# RainbowClock.net
KiCad netlist of a schematic drawn in Altium Designer
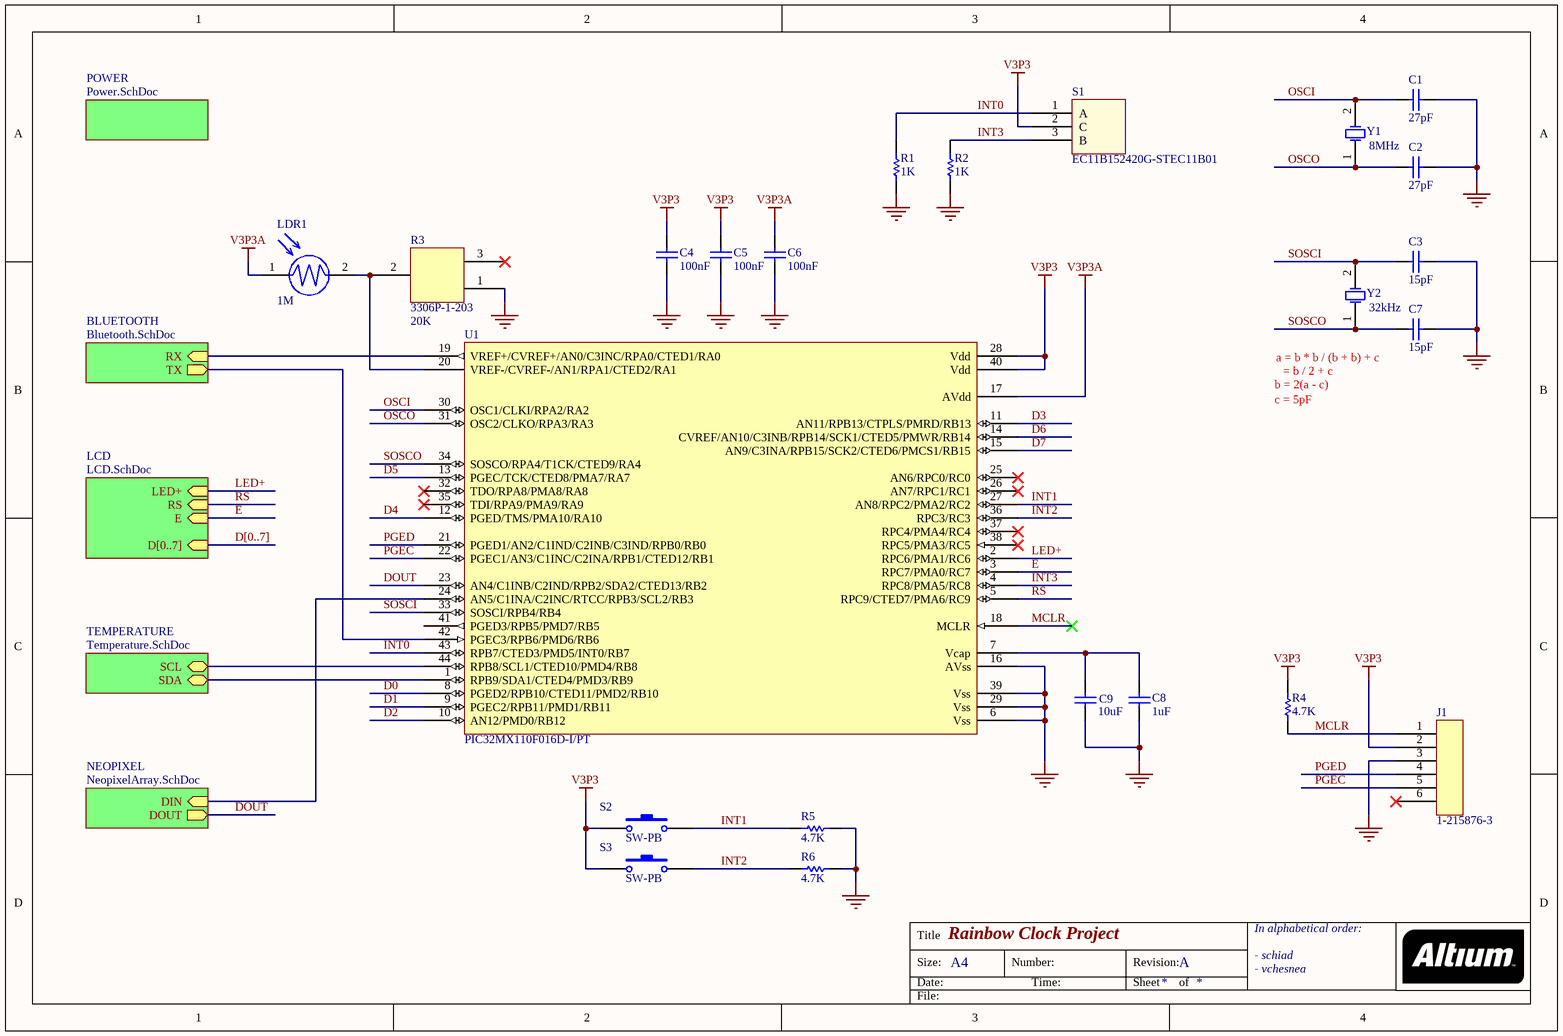
[diagram p0: RainbowClock.SchDoc]

(export (version "E")
  (design (tool "Eeschema 10.0.6"))
  (components
    (comp (ref "C1")
      (value "27pF")
      (footprint "CAP0603")
      (description "Capacitor")
      (libsource (lib "Miscellaneous Devices") (part "Cap"))
    )
    (comp (ref "C2")
      (value "27pF")
      (footprint "CAP0603")
      (description "Capacitor")
      (libsource (lib "Miscellaneous Devices") (part "Cap"))
    )
    (comp (ref "C3")
      (value "15pF")
      (footprint "CAP0603")
      (description "Capacitor")
      (libsource (lib "Miscellaneous Devices") (part "Cap"))
    )
    (comp (ref "C4")
      (value "100nF")
      (footprint "CAP0603")
      (description "Capacitor")
      (libsource (lib "Miscellaneous Devices") (part "Cap"))
    )
    (comp (ref "C5")
      (value "100nF")
      (footprint "CAP0603")
      (description "Capacitor")
      (libsource (lib "Miscellaneous Devices") (part "Cap"))
    )
    (comp (ref "C6")
      (value "100nF")
      (footprint "CAP0603")
      (description "Capacitor")
      (libsource (lib "Miscellaneous Devices") (part "Cap"))
    )
    (comp (ref "C7")
      (value "15pF")
      (footprint "CAP0603")
      (description "Capacitor")
      (libsource (lib "Miscellaneous Devices") (part "Cap"))
    )
    (comp (ref "C8")
      (value "1uF")
      (footprint "CAP0603")
      (description "Capacitor")
      (libsource (lib "Miscellaneous Devices") (part "Cap"))
    )
    (comp (ref "C9")
      (value "10uF")
      (footprint "CAP0603")
      (description "Capacitor")
      (libsource (lib "Miscellaneous Devices") (part "Cap"))
    )
    (comp (ref "J1")
      (value "1-215876-3")
      (footprint "1-215876-3")
      (description "Tyco 1-215876-3")
      (libsource (lib "Components") (part "1-215876-3"))
    )
    (comp (ref "LDR1")
      (value "1M")
      (footprint "VT935G")
      (description "Photoresistor")
      (fields (field (name "Comment") "LDR"))
      (libsource (lib "Components") (part "LDR"))
    )
    (comp (ref "R1")
      (value "1K")
      (footprint "RES0603")
      (description "Resistor")
      (libsource (lib "Miscellaneous Devices") (part "Res1"))
    )
    (comp (ref "R2")
      (value "1K")
      (footprint "RES0603")
      (description "Resistor")
      (libsource (lib "Miscellaneous Devices") (part "Res1"))
    )
    (comp (ref "R3")
      (value "3306P-1-203")
      (footprint "3306P-1-202")
      (description "Trimpot")
      (fields (field (name "ALTIUM_VALUE") "20K"))
      (libsource (lib "Components") (part "3306P-1-202"))
    )
    (comp (ref "R4")
      (value "4.7K")
      (footprint "RES0603")
      (description "Resistor")
      (libsource (lib "Miscellaneous Devices") (part "Res1"))
    )
    (comp (ref "R5")
      (value "4.7K")
      (footprint "RES0603")
      (description "Resistor")
      (libsource (lib "Miscellaneous Devices") (part "Res1"))
    )
    (comp (ref "R6")
      (value "4.7K")
      (footprint "RES0603")
      (description "Resistor")
      (libsource (lib "Miscellaneous Devices") (part "Res1"))
    )
    (comp (ref "S1")
      (value "EC11B152420G-STEC11B01")
      (footprint "EC11B152420G-STEC11B01")
      (description "Rotary encoder")
      (libsource (lib "Components") (part "EC11B152420G-STEC11B01"))
    )
    (comp (ref "S2")
      (value "SW-PB")
      (footprint "1-1825027-4")
      (description "Switch")
      (libsource (lib "Miscellaneous Devices") (part "SW-PB"))
    )
    (comp (ref "S3")
      (value "SW-PB")
      (footprint "1-1825027-4")
      (description "Switch")
      (libsource (lib "Miscellaneous Devices") (part "SW-PB"))
    )
    (comp (ref "U1")
      (value "PIC32MX110F016D-I/PT")
      (footprint "PIC32MX110F016H-I/PT")
      (description "Microcontroller")
      (libsource (lib "Components") (part "PIC32MX110F016D-I/PT"))
    )
    (comp (ref "Y1")
      (value "8MHz")
      (footprint "FOXSLF/080-20")
      (description "Crystal Oscillator")
      (fields (field (name "Comment") "8MHz XTAL"))
      (libsource (lib "Miscellaneous Devices") (part "XTAL"))
    )
    (comp (ref "Y2")
      (value "32kHz")
      (footprint "NCL38LF")
      (description "Crystal Oscillator")
      (fields (field (name "Comment") "32kHz XTAL"))
      (libsource (lib "Miscellaneous Devices") (part "XTAL"))
    )
  )
  (nets
    (net (code "1") (name "/D0") (class "Default")
      (node (ref "U1") (pin "8") (pinfunction "PGED2/RPB10/CTED11/PMD2/RB10_8") (pintype "bidirectional"))
    )
    (net (code "2") (name "/D1") (class "Default")
      (node (ref "U1") (pin "9") (pinfunction "PGEC2/RPB11/PMD1/RB11_9") (pintype "bidirectional"))
    )
    (net (code "3") (name "/D2") (class "Default")
      (node (ref "U1") (pin "10") (pinfunction "AN12/PMD0/RB12_10") (pintype "bidirectional"))
    )
    (net (code "4") (name "/D3") (class "Default")
      (node (ref "U1") (pin "11") (pinfunction "AN11/RPB13/CTPLS/PMRD/RB13_11") (pintype "bidirectional"))
    )
    (net (code "5") (name "/D4") (class "Default")
      (node (ref "U1") (pin "12") (pinfunction "PGED/TMS/PMA10/RA10_12") (pintype "bidirectional"))
    )
    (net (code "6") (name "/D5") (class "Default")
      (node (ref "U1") (pin "13") (pinfunction "PGEC/TCK/CTED8/PMA7/RA7_13") (pintype "bidirectional"))
    )
    (net (code "7") (name "/D6") (class "Default")
      (node (ref "U1") (pin "14") (pinfunction "CVREF/AN10/C3INB/RPB14/SCK1/CTED5/PMWR/RB14_14") (pintype "bidirectional"))
    )
    (net (code "8") (name "/D7") (class "Default")
      (node (ref "U1") (pin "15") (pinfunction "AN9/C3INA/RPB15/SCK2/CTED6/PMCS1/RB15_15") (pintype "bidirectional"))
    )
    (net (code "9") (name "/DIN") (class "Default")
      (node (ref "U1") (pin "24") (pinfunction "AN5/C1INA/C2INC/RTCC/RPB3/SCL2/RB3_24") (pintype "bidirectional"))
    )
    (net (code "10") (name "/DOUT") (class "Default")
      (node (ref "U1") (pin "23") (pinfunction "AN4/C1INB/C2IND/RPB2/SDA2/CTED13/RB2_23") (pintype "bidirectional"))
    )
    (net (code "12") (name "/E") (class "Default")
      (node (ref "U1") (pin "3") (pinfunction "RPC7/PMA0/RC7_3") (pintype "bidirectional"))
    )
    (net (code "13") (name "/INT0") (class "Default")
      (node (ref "R1") (pin "1") (pinfunction "1_1") (pintype "passive"))
      (node (ref "S1") (pin "1") (pinfunction "A_1") (pintype "passive"))
      (node (ref "U1") (pin "43") (pinfunction "RPB7/CTED3/PMD5/INT0/RB7_43") (pintype "bidirectional"))
    )
    (net (code "14") (name "/INT1") (class "Default")
      (node (ref "R5") (pin "2") (pinfunction "2_2") (pintype "passive"))
      (node (ref "S2") (pin "2") (pinfunction "2_2") (pintype "passive"))
      (node (ref "U1") (pin "27") (pinfunction "AN8/RPC2/PMA2/RC2_27") (pintype "bidirectional"))
    )
    (net (code "15") (name "/INT2") (class "Default")
      (node (ref "R6") (pin "2") (pinfunction "2_2") (pintype "passive"))
      (node (ref "S3") (pin "1") (pinfunction "1_1") (pintype "passive"))
      (node (ref "U1") (pin "36") (pinfunction "RPC3/RC3_36") (pintype "bidirectional"))
    )
    (net (code "16") (name "/INT3") (class "Default")
      (node (ref "R2") (pin "2") (pinfunction "2_2") (pintype "passive"))
      (node (ref "S1") (pin "3") (pinfunction "B_3") (pintype "passive"))
      (node (ref "U1") (pin "4") (pinfunction "RPC8/PMA5/RC8_4") (pintype "bidirectional"))
    )
    (net (code "17") (name "/LED+") (class "Default")
      (node (ref "U1") (pin "2") (pinfunction "RPC6/PMA1/RC6_2") (pintype "bidirectional"))
    )
    (net (code "18") (name "/MCLR") (class "Default")
      (node (ref "J1") (pin "1") (pintype "passive"))
      (node (ref "R4") (pin "1") (pinfunction "1_1") (pintype "passive"))
      (node (ref "U1") (pin "18") (pinfunction "MCLR_18") (pintype "input"))
    )
    (net (code "19") (name "/OSCI") (class "Default")
      (node (ref "C1") (pin "1") (pinfunction "1_1") (pintype "passive"))
      (node (ref "U1") (pin "30") (pinfunction "OSC1/CLKI/RPA2/RA2_30") (pintype "bidirectional"))
      (node (ref "Y1") (pin "2") (pinfunction "OSC2_2") (pintype "passive"))
    )
    (net (code "20") (name "/OSCO") (class "Default")
      (node (ref "C2") (pin "1") (pinfunction "1_1") (pintype "passive"))
      (node (ref "U1") (pin "31") (pinfunction "OSC2/CLKO/RPA3/RA3_31") (pintype "bidirectional"))
      (node (ref "Y1") (pin "1") (pinfunction "OSC1_1") (pintype "passive"))
    )
    (net (code "21") (name "/PGEC") (class "Default")
      (node (ref "J1") (pin "5") (pintype "passive"))
      (node (ref "U1") (pin "22") (pinfunction "PGEC1/AN3/C1INC/C2INA/RPB1/CTED12/RB1_22") (pintype "bidirectional"))
    )
    (net (code "22") (name "/PGED") (class "Default")
      (node (ref "J1") (pin "4") (pintype "passive"))
      (node (ref "U1") (pin "21") (pinfunction "PGED1/AN2/C1IND/C2INB/C3IND/RPB0/RB0_21") (pintype "bidirectional"))
    )
    (net (code "23") (name "/RS") (class "Default")
      (node (ref "U1") (pin "5") (pinfunction "RPC9/CTED7/PMA6/RC9_5") (pintype "bidirectional"))
    )
    (net (code "24") (name "/RX") (class "Default")
      (node (ref "U1") (pin "19") (pinfunction "VREF+/CVREF+/AN0/C3INC/RPA0/CTED1/RA0_19") (pintype "output"))
    )
    (net (code "25") (name "/SCL") (class "Default")
      (node (ref "U1") (pin "44") (pinfunction "RPB8/SCL1/CTED10/PMD4/RB8_44") (pintype "bidirectional"))
    )
    (net (code "26") (name "/SDA") (class "Default")
      (node (ref "U1") (pin "1") (pinfunction "RPB9/SDA1/CTED4/PMD3/RB9_1") (pintype "bidirectional"))
    )
    (net (code "27") (name "/SOSCI") (class "Default")
      (node (ref "C3") (pin "1") (pinfunction "1_1") (pintype "passive"))
      (node (ref "U1") (pin "33") (pinfunction "SOSCI/RPB4/RB4_33") (pintype "bidirectional"))
      (node (ref "Y2") (pin "2") (pinfunction "OSC2_2") (pintype "passive"))
    )
    (net (code "28") (name "/SOSCO") (class "Default")
      (node (ref "C7") (pin "1") (pinfunction "1_1") (pintype "passive"))
      (node (ref "U1") (pin "34") (pinfunction "SOSCO/RPA4/T1CK/CTED9/RA4_34") (pintype "bidirectional"))
      (node (ref "Y2") (pin "1") (pinfunction "OSC1_1") (pintype "passive"))
    )
    (net (code "29") (name "/TX") (class "Default")
      (node (ref "U1") (pin "42") (pinfunction "PGEC3/RPB6/PMD6/RB6_42") (pintype "input"))
    )
    (net (code "30") (name "GND") (class "Default")
      (node (ref "C1") (pin "2") (pinfunction "2_2") (pintype "passive"))
      (node (ref "C2") (pin "2") (pinfunction "2_2") (pintype "passive"))
      (node (ref "C3") (pin "2") (pinfunction "2_2") (pintype "passive"))
      (node (ref "C4") (pin "1") (pinfunction "1_1") (pintype "passive"))
      (node (ref "C5") (pin "1") (pinfunction "1_1") (pintype "passive"))
      (node (ref "C6") (pin "1") (pinfunction "1_1") (pintype "passive"))
      (node (ref "C7") (pin "2") (pinfunction "2_2") (pintype "passive"))
      (node (ref "C8") (pin "1") (pinfunction "1_1") (pintype "passive"))
      (node (ref "C9") (pin "1") (pinfunction "1_1") (pintype "passive"))
      (node (ref "J1") (pin "3") (pintype "passive"))
      (node (ref "R1") (pin "2") (pinfunction "2_2") (pintype "passive"))
      (node (ref "R2") (pin "1") (pinfunction "1_1") (pintype "passive"))
      (node (ref "R3") (pin "1") (pinfunction "1_1") (pintype "power_in"))
      (node (ref "R5") (pin "1") (pinfunction "1_1") (pintype "passive"))
      (node (ref "R6") (pin "1") (pinfunction "1_1") (pintype "passive"))
      (node (ref "U1") (pin "16") (pinfunction "AVss_16") (pintype "power_in"))
      (node (ref "U1") (pin "29") (pinfunction "Vss_29") (pintype "power_in"))
      (node (ref "U1") (pin "39") (pinfunction "Vss_39") (pintype "power_in"))
      (node (ref "U1") (pin "6") (pinfunction "Vss_6") (pintype "passive"))
    )
    (net (code "31") (name "Net-(U1-VREF-{slash}CVREF-{slash}AN1{slash}RPA1{slash}CTED2{slash}RA1)") (class "Default")
      (node (ref "LDR1") (pin "2") (pinfunction "2_2") (pintype "power_in"))
      (node (ref "R3") (pin "2") (pinfunction "2_2") (pintype "power_in"))
      (node (ref "U1") (pin "20") (pinfunction "VREF-/CVREF-/AN1/RPA1/CTED2/RA1_20") (pintype "passive"))
    )
    (net (code "32") (name "Net-(U1-Vcap)") (class "Default")
      (node (ref "C8") (pin "2") (pinfunction "2_2") (pintype "passive"))
      (node (ref "C9") (pin "2") (pinfunction "2_2") (pintype "passive"))
      (node (ref "U1") (pin "7") (pinfunction "Vcap_7") (pintype "passive"))
    )
    (net (code "33") (name "V3P3") (class "Default")
      (node (ref "C4") (pin "2") (pinfunction "2_2") (pintype "passive"))
      (node (ref "C5") (pin "2") (pinfunction "2_2") (pintype "passive"))
      (node (ref "J1") (pin "2") (pintype "passive"))
      (node (ref "R4") (pin "2") (pinfunction "2_2") (pintype "passive"))
      (node (ref "S1") (pin "2") (pinfunction "C_2") (pintype "passive"))
      (node (ref "S2") (pin "1") (pinfunction "1_1") (pintype "passive"))
      (node (ref "S3") (pin "2") (pinfunction "2_2") (pintype "passive"))
      (node (ref "U1") (pin "28") (pinfunction "Vdd_28") (pintype "power_in"))
      (node (ref "U1") (pin "40") (pinfunction "Vdd_40") (pintype "power_in"))
    )
    (net (code "34") (name "V3P3A") (class "Default")
      (node (ref "C6") (pin "2") (pinfunction "2_2") (pintype "passive"))
      (node (ref "LDR1") (pin "1") (pinfunction "1_1") (pintype "power_in"))
      (node (ref "U1") (pin "17") (pinfunction "AVdd_17") (pintype "power_in"))
    )
    (net (code "35") (name "unconnected-(J1-Pad6)") (class "Default")
      (node (ref "J1") (pin "6") (pintype "passive+no_connect"))
    )
    (net (code "36") (name "unconnected-(R3-Pad3)") (class "Default")
      (node (ref "R3") (pin "3") (pinfunction "3_3") (pintype "power_in+no_connect"))
    )
    (net (code "37") (name "unconnected-(U1-AN6{slash}RPC0{slash}RC0-Pad25)") (class "Default")
      (node (ref "U1") (pin "25") (pinfunction "AN6/RPC0/RC0_25") (pintype "bidirectional+no_connect"))
    )
    (net (code "38") (name "unconnected-(U1-AN7{slash}RPC1{slash}RC1-Pad26)") (class "Default")
      (node (ref "U1") (pin "26") (pinfunction "AN7/RPC1/RC1_26") (pintype "bidirectional+no_connect"))
    )
    (net (code "39") (name "unconnected-(U1-PGED3{slash}RPB5{slash}PMD7{slash}RB5-Pad41)") (class "Default")
      (node (ref "U1") (pin "41") (pinfunction "PGED3/RPB5/PMD7/RB5_41") (pintype "output"))
    )
    (net (code "40") (name "unconnected-(U1-RPC4{slash}PMA4{slash}RC4-Pad37)") (class "Default")
      (node (ref "U1") (pin "37") (pinfunction "RPC4/PMA4/RC4_37") (pintype "bidirectional+no_connect"))
    )
    (net (code "41") (name "unconnected-(U1-RPC5{slash}PMA3{slash}RC5-Pad38)") (class "Default")
      (node (ref "U1") (pin "38") (pinfunction "RPC5/PMA3/RC5_38") (pintype "input+no_connect"))
    )
    (net (code "42") (name "unconnected-(U1-TDI{slash}RPA9{slash}PMA9{slash}RA9-Pad35)") (class "Default")
      (node (ref "U1") (pin "35") (pinfunction "TDI/RPA9/PMA9/RA9_35") (pintype "bidirectional+no_connect"))
    )
    (net (code "43") (name "unconnected-(U1-TDO{slash}RPA8{slash}PMA8{slash}RA8-Pad32)") (class "Default")
      (node (ref "U1") (pin "32") (pinfunction "TDO/RPA8/PMA8/RA8_32") (pintype "bidirectional+no_connect"))
    )
  )
)
